# TSSP_Mini_Board.net
KiCad netlist of a schematic drawn in EAGLE
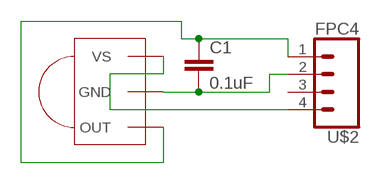
[diagram p0: schematic, sheet 1]

(export (version "E")
  (design (tool "Eeschema 10.0.6"))
  (components
    (comp (ref "C1")
      (value "0.1uF")
      (footprint "eagle-import:0603")
      (libsource (lib "eagle-import") (part "0.1UF-0603-25V-5%"))
    )
    (comp (ref "U$1")
      (value "TSSP58038")
      (footprint "eagle-import:MINICAST")
      (libsource (lib "eagle-import") (part "TSSP58038"))
    )
    (comp (ref "U$2")
      (value "FPC4")
      (footprint "eagle-import:FPC4")
      (libsource (lib "eagle-import") (part "FPC4"))
    )
  )
  (nets
    (net (code "1") (name "Net-(U$1-GND)") (class "Default")
      (node (ref "C1") (pin "2") (pinfunction "2_2") (pintype "passive"))
      (node (ref "U$1") (pin "2") (pinfunction "GND_2") (pintype "bidirectional"))
      (node (ref "U$2") (pin "2") (pinfunction "2_2") (pintype "passive"))
    )
    (net (code "2") (name "Net-(U$1-OUT)") (class "Default")
      (node (ref "C1") (pin "1") (pinfunction "1_1") (pintype "passive"))
      (node (ref "U$1") (pin "1") (pinfunction "OUT_1") (pintype "bidirectional"))
      (node (ref "U$2") (pin "1") (pinfunction "1_1") (pintype "passive"))
    )
    (net (code "3") (name "Net-(U$1-VS)") (class "Default")
      (node (ref "U$1") (pin "3") (pinfunction "VS_3") (pintype "bidirectional"))
      (node (ref "U$2") (pin "4") (pinfunction "4_4") (pintype "passive"))
    )
    (net (code "4") (name "unconnected-(U$2-Pad3)") (class "Default")
      (node (ref "U$2") (pin "3") (pinfunction "3_3") (pintype "passive"))
    )
  )
)
